# DM2097_RIGHT_OV9282.net
KiCad netlist of a schematic drawn in Altium Designer
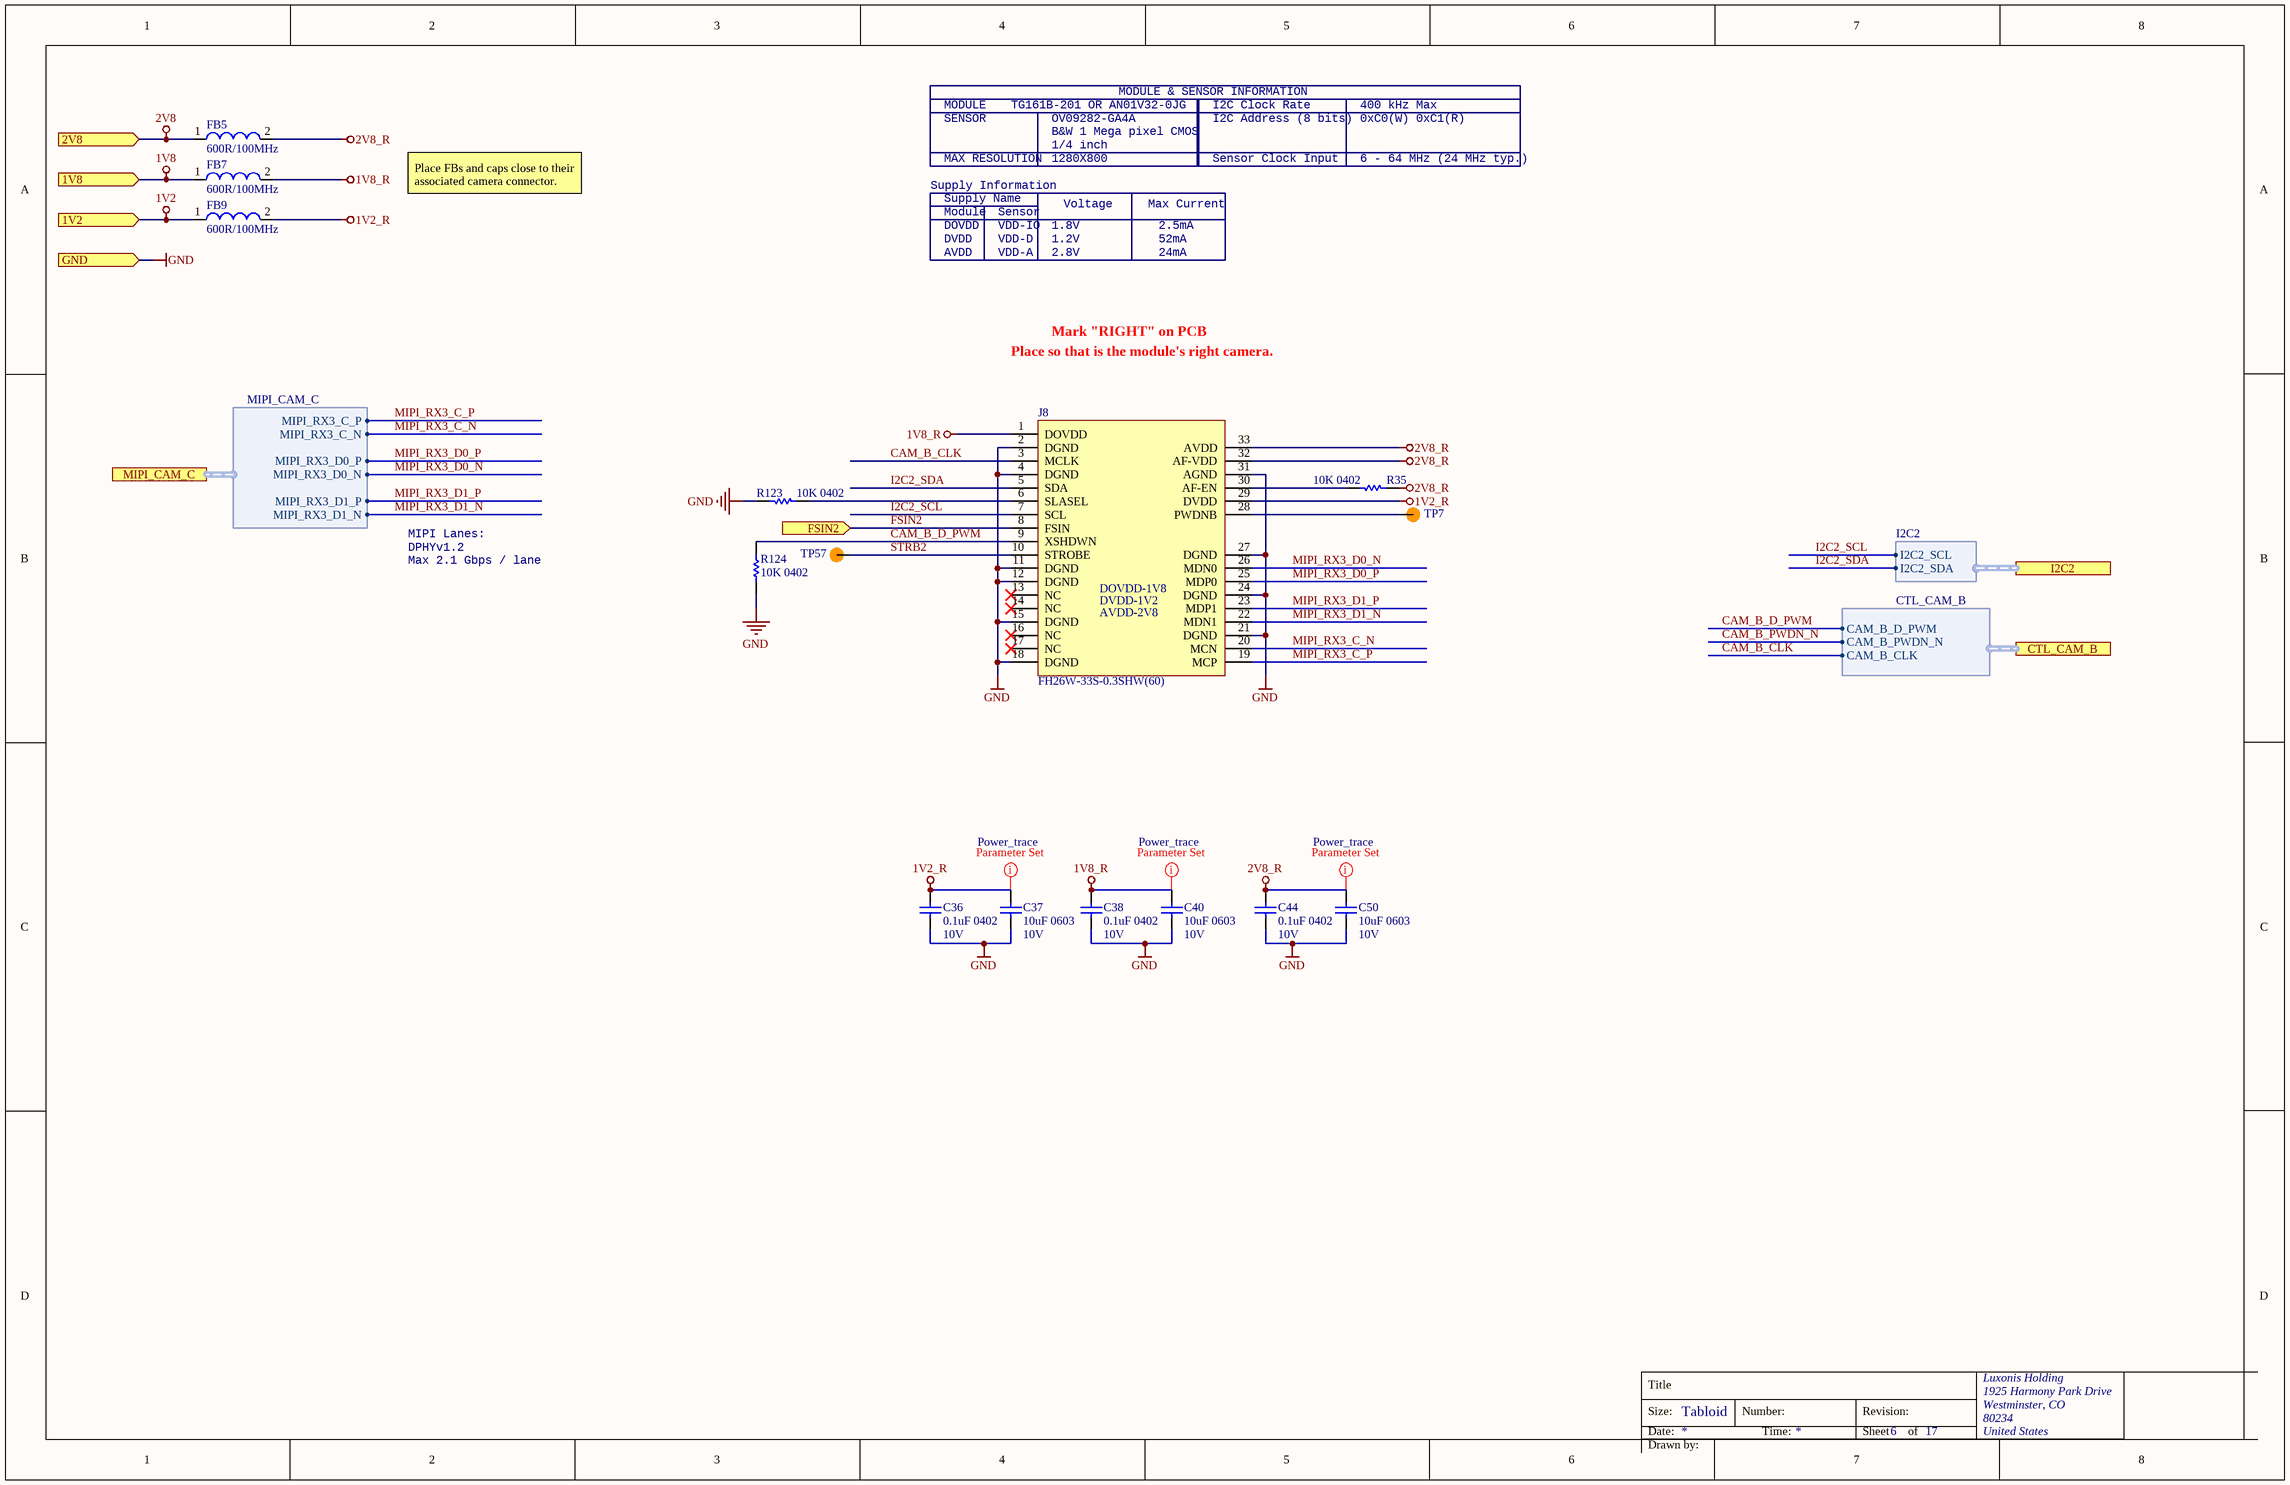
[diagram p0: DM2097_RIGHT_OV9282.SchDoc]

(export (version "E")
  (design (tool "Eeschema 10.0.6"))
  (components
    (comp (ref "C36")
      (value "0.1uF 0402")
      (footprint "CAP_Altium_Vault_Generic:CAPC0402(1005)70_L")
      (description "CAP CER 0.1UF 10V X7R 0402 5%")
      (fields (field (name "TOLERANCE") "5%") (field (name "VOLTAGE RATING") "10V"))
      (libsource (lib "LuxonisMaster") (part "GRM155R71A104JA01D"))
    )
    (comp (ref "C37")
      (value "10uF 0603")
      (footprint "CAP_Altium_Vault_Generic:CAPC0603(1608)100_L")
      (description "CAP CER 10UF 10V X5R 0603 20%")
      (fields (field (name "TOLERANCE") "20%") (field (name "VOLTAGE RATING") "10V"))
      (libsource (lib "LuxonisMaster") (part "GRM188R61A106ME69D"))
    )
    (comp (ref "C38")
      (value "0.1uF 0402")
      (footprint "CAP_Altium_Vault_Generic:CAPC0402(1005)70_L")
      (description "CAP CER 0.1UF 10V X7R 0402 5%")
      (fields (field (name "TOLERANCE") "5%") (field (name "VOLTAGE RATING") "10V"))
      (libsource (lib "LuxonisMaster") (part "GRM155R71A104JA01D"))
    )
    (comp (ref "C40")
      (value "10uF 0603")
      (footprint "CAP_Altium_Vault_Generic:CAPC0603(1608)100_L")
      (description "CAP CER 10UF 10V X5R 0603 20%")
      (fields (field (name "TOLERANCE") "20%") (field (name "VOLTAGE RATING") "10V"))
      (libsource (lib "LuxonisMaster") (part "GRM188R61A106ME69D"))
    )
    (comp (ref "C44")
      (value "0.1uF 0402")
      (footprint "CAP_Altium_Vault_Generic:CAPC0402(1005)70_L")
      (description "CAP CER 0.1UF 10V X7R 0402 5%")
      (fields (field (name "TOLERANCE") "5%") (field (name "VOLTAGE RATING") "10V"))
      (libsource (lib "LuxonisMaster") (part "GRM155R71A104JA01D"))
    )
    (comp (ref "C50")
      (value "10uF 0603")
      (footprint "CAP_Altium_Vault_Generic:CAPC0603(1608)100_L")
      (description "CAP CER 10UF 10V X5R 0603 20%")
      (fields (field (name "TOLERANCE") "20%") (field (name "VOLTAGE RATING") "10V"))
      (libsource (lib "LuxonisMaster") (part "GRM188R61A106ME69D"))
    )
    (comp (ref "FB5")
      (value "600R/100MHz")
      (footprint "LuxonisMaster:2508056017Y2")
      (description "FERRITE BEAD, 0.1OHM, 2A, 0805, 600R/100MHz")
      (fields (field (name "TOLERANCE") "25%"))
      (libsource (lib "LuxonisMaster") (part "2508056017Y2"))
    )
    (comp (ref "FB7")
      (value "600R/100MHz")
      (footprint "LuxonisMaster:2508056017Y2")
      (description "FERRITE BEAD, 0.1OHM, 2A, 0805, 600R/100MHz")
      (fields (field (name "TOLERANCE") "25%"))
      (libsource (lib "LuxonisMaster") (part "2508056017Y2"))
    )
    (comp (ref "FB9")
      (value "600R/100MHz")
      (footprint "LuxonisMaster:2508056017Y2")
      (description "FERRITE BEAD, 0.1OHM, 2A, 0805, 600R/100MHz")
      (fields (field (name "TOLERANCE") "25%"))
      (libsource (lib "LuxonisMaster") (part "2508056017Y2"))
    )
    (comp (ref "J8")
      (value "FH26W-33S-0.3SHW(60)")
      (footprint "AC-PY003-OV9282")
      (description "FFC/FPC Connector, 33 Contact(s), 1 Row(s), Female, Right Angle, Surface Mount Terminal")
      (libsource (lib "DM9098") (part "AC_PY003-OV9282_CON"))
    )
    (comp (ref "R35")
      (value "10K 0402")
      (footprint "RES_Altium_Vault_Generic:RESC0402(1005)_L")
      (fields (field (name "TOLERANCE") "1%"))
      (libsource (lib "LuxonisMaster") (part "RC0402FR-1310KL"))
    )
    (comp (ref "R123")
      (value "10K 0402")
      (footprint "RES_Altium_Vault_Generic:RESC0402(1005)_L")
      (fields (field (name "TOLERANCE") "1%"))
      (libsource (lib "LuxonisMaster") (part "RC0402FR-1310KL"))
    )
    (comp (ref "R124")
      (value "10K 0402")
      (footprint "RES_Altium_Vault_Generic:RESC0402(1005)_L")
      (fields (field (name "TOLERANCE") "1%"))
      (libsource (lib "LuxonisMaster") (part "RC0402FR-1310KL"))
    )
    (comp (ref "TP7")
      (value "TP100_200_NS")
      (footprint "LuxonisMaster:TP100_200_NS")
      (libsource (lib "LuxonisMaster") (part "TEST_POINT"))
    )
    (comp (ref "TP57")
      (value "TP100_200_NS")
      (footprint "LuxonisMaster:TP100_200_NS")
      (libsource (lib "LuxonisMaster") (part "TEST_POINT"))
    )
  )
  (nets
    (net (code "4") (name "/CAM_B_CLK") (class "Default")
      (node (ref "J8") (pin "3") (pinfunction "MCLK_3") (pintype "passive"))
    )
    (net (code "5") (name "/CAM_B_D_PWM") (class "Default")
      (node (ref "J8") (pin "9") (pinfunction "XSHDWN_9") (pintype "passive"))
      (node (ref "R124") (pin "2") (pinfunction "2_2") (pintype "passive"))
    )
    (net (code "7") (name "/FSIN2") (class "Default")
      (node (ref "J8") (pin "8") (pinfunction "FSIN_8") (pintype "passive"))
    )
    (net (code "8") (name "/I2C2_SCL") (class "Default")
      (node (ref "J8") (pin "7") (pinfunction "SCL_7") (pintype "passive"))
    )
    (net (code "9") (name "/I2C2_SDA") (class "Default")
      (node (ref "J8") (pin "5") (pinfunction "SDA_5") (pintype "passive"))
    )
    (net (code "10") (name "/MIPI_RX3_C_N") (class "Default")
      (node (ref "J8") (pin "20") (pinfunction "MCN_20") (pintype "passive"))
    )
    (net (code "11") (name "/MIPI_RX3_C_P") (class "Default")
      (node (ref "J8") (pin "19") (pinfunction "MCP_19") (pintype "passive"))
    )
    (net (code "12") (name "/MIPI_RX3_D0_N") (class "Default")
      (node (ref "J8") (pin "26") (pinfunction "MDN0_26") (pintype "passive"))
    )
    (net (code "13") (name "/MIPI_RX3_D0_P") (class "Default")
      (node (ref "J8") (pin "25") (pinfunction "MDP0_25") (pintype "passive"))
    )
    (net (code "14") (name "/MIPI_RX3_D1_N") (class "Default")
      (node (ref "J8") (pin "22") (pinfunction "MDN1_22") (pintype "passive"))
    )
    (net (code "15") (name "/MIPI_RX3_D1_P") (class "Default")
      (node (ref "J8") (pin "23") (pinfunction "MDP1_23") (pintype "passive"))
    )
    (net (code "16") (name "/STRB2") (class "Default")
      (node (ref "J8") (pin "10") (pinfunction "STROBE_10") (pintype "passive"))
      (node (ref "TP57") (pin "1") (pintype "passive"))
    )
    (net (code "20") (name "1V2") (class "Default")
      (node (ref "FB9") (pin "1") (pinfunction "1_1") (pintype "passive"))
    )
    (net (code "21") (name "1V2_R") (class "Default")
      (node (ref "C36") (pin "2") (pinfunction "2_2") (pintype "passive"))
      (node (ref "C37") (pin "2") (pinfunction "2_2") (pintype "passive"))
      (node (ref "FB9") (pin "2") (pinfunction "2_2") (pintype "passive"))
      (node (ref "J8") (pin "29") (pinfunction "DVDD_29") (pintype "passive"))
    )
    (net (code "22") (name "1V8") (class "Default")
      (node (ref "FB7") (pin "1") (pinfunction "1_1") (pintype "passive"))
    )
    (net (code "23") (name "1V8_R") (class "Default")
      (node (ref "C38") (pin "2") (pinfunction "2_2") (pintype "passive"))
      (node (ref "C40") (pin "2") (pinfunction "2_2") (pintype "passive"))
      (node (ref "FB7") (pin "2") (pinfunction "2_2") (pintype "passive"))
      (node (ref "J8") (pin "1") (pinfunction "DOVDD_1") (pintype "passive"))
    )
    (net (code "24") (name "2V8") (class "Default")
      (node (ref "FB5") (pin "1") (pinfunction "1_1") (pintype "passive"))
    )
    (net (code "25") (name "2V8_R") (class "Default")
      (node (ref "C44") (pin "2") (pinfunction "2_2") (pintype "passive"))
      (node (ref "C50") (pin "2") (pinfunction "2_2") (pintype "passive"))
      (node (ref "FB5") (pin "2") (pinfunction "2_2") (pintype "passive"))
      (node (ref "J8") (pin "32") (pinfunction "AF-VDD_32") (pintype "passive"))
      (node (ref "J8") (pin "33") (pinfunction "AVDD_33") (pintype "passive"))
      (node (ref "R35") (pin "2") (pinfunction "2_2") (pintype "passive"))
    )
    (net (code "26") (name "GND") (class "Default")
      (node (ref "C36") (pin "1") (pinfunction "1_1") (pintype "passive"))
      (node (ref "C37") (pin "1") (pinfunction "1_1") (pintype "passive"))
      (node (ref "C38") (pin "1") (pinfunction "1_1") (pintype "passive"))
      (node (ref "C40") (pin "1") (pinfunction "1_1") (pintype "passive"))
      (node (ref "C44") (pin "1") (pinfunction "1_1") (pintype "passive"))
      (node (ref "C50") (pin "1") (pinfunction "1_1") (pintype "passive"))
      (node (ref "J8") (pin "11") (pinfunction "DGND_11") (pintype "passive"))
      (node (ref "J8") (pin "12") (pinfunction "DGND_12") (pintype "passive"))
      (node (ref "J8") (pin "15") (pinfunction "DGND_15") (pintype "passive"))
      (node (ref "J8") (pin "18") (pinfunction "DGND_18") (pintype "passive"))
      (node (ref "J8") (pin "2") (pinfunction "DGND_2") (pintype "passive"))
      (node (ref "J8") (pin "21") (pinfunction "DGND_21") (pintype "passive"))
      (node (ref "J8") (pin "24") (pinfunction "DGND_24") (pintype "passive"))
      (node (ref "J8") (pin "27") (pinfunction "DGND_27") (pintype "passive"))
      (node (ref "J8") (pin "31") (pinfunction "AGND_31") (pintype "passive"))
      (node (ref "J8") (pin "4") (pinfunction "DGND_4") (pintype "passive"))
      (node (ref "R123") (pin "1") (pinfunction "1_1") (pintype "passive"))
      (node (ref "R124") (pin "1") (pinfunction "1_1") (pintype "passive"))
    )
    (net (code "27") (name "Net-(J8-AF-EN)") (class "Default")
      (node (ref "J8") (pin "30") (pinfunction "AF-EN_30") (pintype "passive"))
      (node (ref "R35") (pin "1") (pinfunction "1_1") (pintype "passive"))
    )
    (net (code "28") (name "Net-(J8-PWDNB)") (class "Default")
      (node (ref "J8") (pin "28") (pinfunction "PWDNB_28") (pintype "passive"))
      (node (ref "TP7") (pin "1") (pintype "passive"))
    )
    (net (code "29") (name "Net-(J8-SLASEL)") (class "Default")
      (node (ref "J8") (pin "6") (pinfunction "SLASEL_6") (pintype "passive"))
      (node (ref "R123") (pin "2") (pinfunction "2_2") (pintype "passive"))
    )
    (net (code "30") (name "unconnected-(J8-NC-Pad13)") (class "Default")
      (node (ref "J8") (pin "13") (pinfunction "NC_13") (pintype "passive+no_connect"))
    )
    (net (code "31") (name "unconnected-(J8-NC-Pad14)") (class "Default")
      (node (ref "J8") (pin "14") (pinfunction "NC_14") (pintype "passive+no_connect"))
    )
    (net (code "32") (name "unconnected-(J8-NC-Pad16)") (class "Default")
      (node (ref "J8") (pin "16") (pinfunction "NC_16") (pintype "passive+no_connect"))
    )
    (net (code "33") (name "unconnected-(J8-NC-Pad17)") (class "Default")
      (node (ref "J8") (pin "17") (pinfunction "NC_17") (pintype "passive+no_connect"))
    )
  )
)
